# 5_Magnetorquer_Drivers.net
KiCad netlist of a schematic drawn in Altium Designer
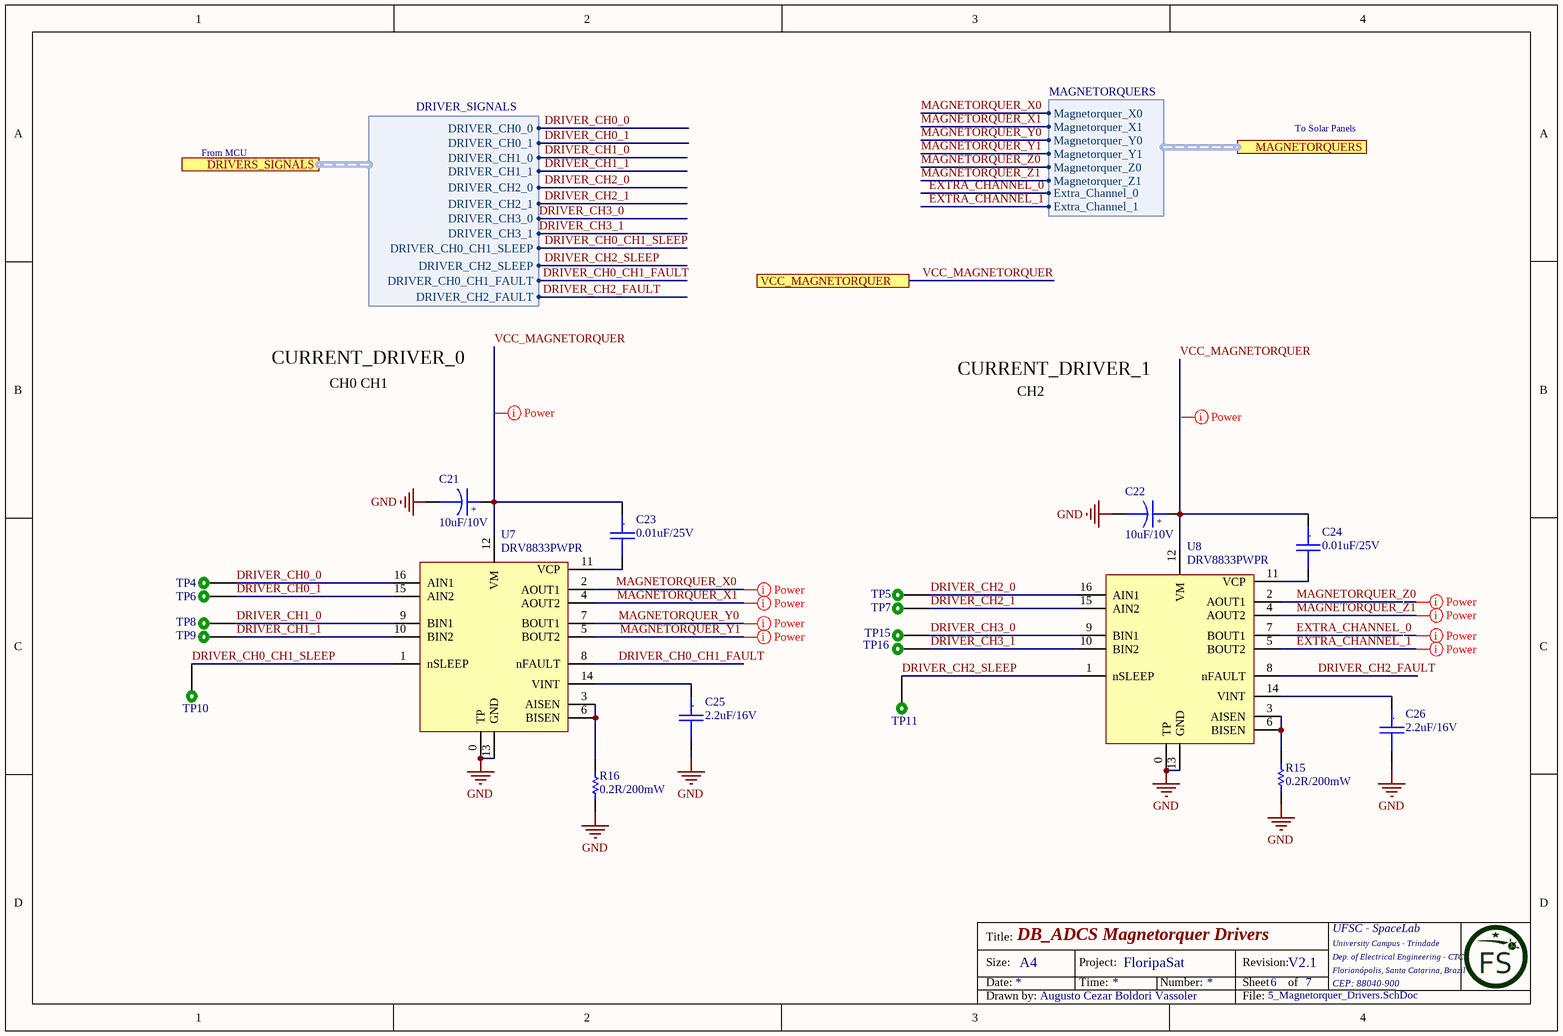
[diagram p0: 5_Magnetorquer_Drivers.SchDoc]

(export (version "E")
  (design (tool "Eeschema 10.0.6"))
  (components
    (comp (ref "C21")
      (value "10uF/10V")
      (footprint "CC0805_Tantalum")
      (description "CAP Tantalum 10uF 6.3V 10% 0805")
      (fields (field (name "PARTNUMBER") "TPSR106K006R1000"))
      (libsource (lib "PCB_Eng_Model_OBDH_2") (part "Cap_Tant_SMD_10uF_6V3_0805"))
    )
    (comp (ref "C22")
      (value "10uF/10V")
      (footprint "CC0805_Tantalum")
      (description "CAP Tantalum 10uF 6.3V 10% 0805")
      (fields (field (name "PARTNUMBER") "TPSR106K006R1000"))
      (libsource (lib "PCB_Eng_Model_OBDH_2") (part "Cap_Tant_SMD_10uF_6V3_0805"))
    )
    (comp (ref "C23")
      (value "0.01uF/25V")
      (footprint "CC0805")
      (description "CAP CER 0.01uF 25V 10% X7R 0805")
      (fields (field (name "PARTNUMBER") "CL21B103KAANNNC"))
      (libsource (lib "PCB_Eng_Model_OBDH_2") (part "Cap_Cer_X7R_0.01uF_50V_0805"))
    )
    (comp (ref "C24")
      (value "0.01uF/25V")
      (footprint "CC0805")
      (description "CAP CER 0.01uF 25V 10% X7R 0805")
      (fields (field (name "PARTNUMBER") "CL21B103KAANNNC"))
      (libsource (lib "PCB_Eng_Model_OBDH_2") (part "Cap_Cer_X7R_0.01uF_50V_0805"))
    )
    (comp (ref "C25")
      (value "2.2uF/16V")
      (footprint "CC0805")
      (description "CAP CER 2.2uF 16V 0805")
      (fields (field (name "PARTNUMBER") "C2012X7R1C225K125AB"))
      (libsource (lib "PCB_Eng_Model_OBDH_2") (part "Cap_Cer_X7R_2.2uF_16V_0805"))
    )
    (comp (ref "C26")
      (value "2.2uF/16V")
      (footprint "CC0805")
      (description "CAP CER 2.2uF 16V 0805")
      (fields (field (name "PARTNUMBER") "C2012X7R1C225K125AB"))
      (libsource (lib "PCB_Eng_Model_OBDH_2") (part "Cap_Cer_X7R_2.2uF_16V_0805"))
    )
    (comp (ref "R15")
      (value "0.2R/200mW")
      (footprint "0805-LED")
      (description "RES 0.2 OHM - 0.2W 1% 0805")
      (fields (field (name "PARTNUMBER") "RL1220S-R20-F"))
      (libsource (lib "PCB_Eng_Model_OBDH_2") (part "R0.015R_1%_0.5W_0805"))
    )
    (comp (ref "R16")
      (value "0.2R/200mW")
      (footprint "0805-LED")
      (description "RES 0.2 OHM - 0.2W 1% 0805")
      (fields (field (name "PARTNUMBER") "RL1220S-R20-F"))
      (libsource (lib "PCB_Eng_Model_OBDH_2") (part "R0.015R_1%_0.5W_0805"))
    )
    (comp (ref "TP4")
      (value "TEST_POINT_2")
      (footprint "TEST_POINT_2")
      (description "Test point")
      (libsource (lib "PCB_Eng_Model_OBDH_2") (part "TEST_POINT_2"))
    )
    (comp (ref "TP5")
      (value "TEST_POINT_2")
      (footprint "TEST_POINT_2")
      (description "Test point")
      (libsource (lib "PCB_Eng_Model_OBDH_2") (part "TEST_POINT_2"))
    )
    (comp (ref "TP6")
      (value "TEST_POINT_2")
      (footprint "TEST_POINT_2")
      (description "Test point")
      (libsource (lib "PCB_Eng_Model_OBDH_2") (part "TEST_POINT_2"))
    )
    (comp (ref "TP7")
      (value "TEST_POINT_2")
      (footprint "TEST_POINT_2")
      (description "Test point")
      (libsource (lib "PCB_Eng_Model_OBDH_2") (part "TEST_POINT_2"))
    )
    (comp (ref "TP8")
      (value "TEST_POINT_2")
      (footprint "TEST_POINT_2")
      (description "Test point")
      (libsource (lib "PCB_Eng_Model_OBDH_2") (part "TEST_POINT_2"))
    )
    (comp (ref "TP9")
      (value "TEST_POINT_2")
      (footprint "TEST_POINT_2")
      (description "Test point")
      (libsource (lib "PCB_Eng_Model_OBDH_2") (part "TEST_POINT_2"))
    )
    (comp (ref "TP10")
      (value "TEST_POINT_2")
      (footprint "TEST_POINT_2")
      (description "Test point")
      (libsource (lib "PCB_Eng_Model_OBDH_2") (part "TEST_POINT_2"))
    )
    (comp (ref "TP11")
      (value "TEST_POINT_2")
      (footprint "TEST_POINT_2")
      (description "Test point")
      (libsource (lib "PCB_Eng_Model_OBDH_2") (part "TEST_POINT_2"))
    )
    (comp (ref "TP15")
      (value "TEST_POINT_2")
      (footprint "TEST_POINT_2")
      (description "Test point")
      (libsource (lib "PCB_DB_ADCS") (part "TEST_POINT_2"))
    )
    (comp (ref "TP16")
      (value "TEST_POINT_2")
      (footprint "TEST_POINT_2")
      (description "Test point")
      (libsource (lib "PCB_DB_ADCS") (part "TEST_POINT_2"))
    )
    (comp (ref "U7")
      (value "DRV8833PWPR")
      (footprint "16TTSSOP")
      (libsource (lib "FloripaSatSchlib") (part "DRV8833PWPR"))
    )
    (comp (ref "U8")
      (value "DRV8833PWPR")
      (footprint "16TTSSOP")
      (libsource (lib "FloripaSatSchlib") (part "DRV8833PWPR"))
    )
  )
  (nets
    (net (code "3") (name "/DRIVER_CH0_0") (class "Default")
      (node (ref "TP4") (pin "1") (pinfunction "1_1") (pintype "passive"))
      (node (ref "U7") (pin "16") (pinfunction "AIN1_16") (pintype "passive"))
    )
    (net (code "4") (name "/DRIVER_CH0_1") (class "Default")
      (node (ref "TP6") (pin "1") (pinfunction "1_1") (pintype "passive"))
      (node (ref "U7") (pin "15") (pinfunction "AIN2_15") (pintype "passive"))
    )
    (net (code "5") (name "/DRIVER_CH0_CH1_FAULT") (class "Default")
      (node (ref "U7") (pin "8") (pinfunction "nFAULT_8") (pintype "passive"))
    )
    (net (code "6") (name "/DRIVER_CH0_CH1_SLEEP") (class "Default")
      (node (ref "TP10") (pin "1") (pinfunction "1_1") (pintype "passive"))
      (node (ref "U7") (pin "1") (pinfunction "nSLEEP_1") (pintype "passive"))
    )
    (net (code "7") (name "/DRIVER_CH1_0") (class "Default")
      (node (ref "TP8") (pin "1") (pinfunction "1_1") (pintype "passive"))
      (node (ref "U7") (pin "9") (pinfunction "BIN1_9") (pintype "passive"))
    )
    (net (code "8") (name "/DRIVER_CH1_1") (class "Default")
      (node (ref "TP9") (pin "1") (pinfunction "1_1") (pintype "passive"))
      (node (ref "U7") (pin "10") (pinfunction "BIN2_10") (pintype "passive"))
    )
    (net (code "9") (name "/DRIVER_CH2_0") (class "Default")
      (node (ref "TP5") (pin "1") (pinfunction "1_1") (pintype "passive"))
      (node (ref "U8") (pin "16") (pinfunction "AIN1_16") (pintype "passive"))
    )
    (net (code "10") (name "/DRIVER_CH2_1") (class "Default")
      (node (ref "TP7") (pin "1") (pinfunction "1_1") (pintype "passive"))
      (node (ref "U8") (pin "15") (pinfunction "AIN2_15") (pintype "passive"))
    )
    (net (code "11") (name "/DRIVER_CH2_FAULT") (class "Default")
      (node (ref "U8") (pin "8") (pinfunction "nFAULT_8") (pintype "passive"))
    )
    (net (code "12") (name "/DRIVER_CH2_SLEEP") (class "Default")
      (node (ref "TP11") (pin "1") (pinfunction "1_1") (pintype "passive"))
      (node (ref "U8") (pin "1") (pinfunction "nSLEEP_1") (pintype "passive"))
    )
    (net (code "13") (name "/DRIVER_CH3_0") (class "Default")
      (node (ref "TP15") (pin "1") (pinfunction "1_1") (pintype "passive"))
      (node (ref "U8") (pin "9") (pinfunction "BIN1_9") (pintype "passive"))
    )
    (net (code "14") (name "/DRIVER_CH3_1") (class "Default")
      (node (ref "TP16") (pin "1") (pinfunction "1_1") (pintype "passive"))
      (node (ref "U8") (pin "10") (pinfunction "BIN2_10") (pintype "passive"))
    )
    (net (code "15") (name "/EXTRA_CHANNEL_0") (class "Default")
      (node (ref "U8") (pin "7") (pinfunction "BOUT1_7") (pintype "passive"))
    )
    (net (code "16") (name "/EXTRA_CHANNEL_1") (class "Default")
      (node (ref "U8") (pin "5") (pinfunction "BOUT2_5") (pintype "passive"))
    )
    (net (code "17") (name "/MAGNETORQUER_X0") (class "Default")
      (node (ref "U7") (pin "2") (pinfunction "AOUT1_2") (pintype "passive"))
    )
    (net (code "18") (name "/MAGNETORQUER_X1") (class "Default")
      (node (ref "U7") (pin "4") (pinfunction "AOUT2_4") (pintype "passive"))
    )
    (net (code "19") (name "/MAGNETORQUER_Y0") (class "Default")
      (node (ref "U7") (pin "7") (pinfunction "BOUT1_7") (pintype "passive"))
    )
    (net (code "20") (name "/MAGNETORQUER_Y1") (class "Default")
      (node (ref "U7") (pin "5") (pinfunction "BOUT2_5") (pintype "passive"))
    )
    (net (code "21") (name "/MAGNETORQUER_Z0") (class "Default")
      (node (ref "U8") (pin "2") (pinfunction "AOUT1_2") (pintype "passive"))
    )
    (net (code "22") (name "/MAGNETORQUER_Z1") (class "Default")
      (node (ref "U8") (pin "4") (pinfunction "AOUT2_4") (pintype "passive"))
    )
    (net (code "23") (name "/VCC_MAGNETORQUER") (class "Default")
      (node (ref "C21") (pin "1") (pinfunction "1_1") (pintype "passive"))
      (node (ref "C22") (pin "1") (pinfunction "1_1") (pintype "passive"))
      (node (ref "C23") (pin "1") (pinfunction "1_1") (pintype "passive"))
      (node (ref "C24") (pin "1") (pinfunction "1_1") (pintype "passive"))
      (node (ref "U7") (pin "12") (pinfunction "VM_12") (pintype "passive"))
      (node (ref "U8") (pin "12") (pinfunction "VM_12") (pintype "passive"))
    )
    (net (code "26") (name "GND") (class "Default")
      (node (ref "C21") (pin "2") (pinfunction "2_2") (pintype "passive"))
      (node (ref "C22") (pin "2") (pinfunction "2_2") (pintype "passive"))
      (node (ref "C25") (pin "2") (pinfunction "2_2") (pintype "passive"))
      (node (ref "C26") (pin "2") (pinfunction "2_2") (pintype "passive"))
      (node (ref "R15") (pin "1") (pinfunction "1_1") (pintype "passive"))
      (node (ref "R16") (pin "1") (pinfunction "1_1") (pintype "passive"))
      (node (ref "U7") (pin "0") (pinfunction "TP_0") (pintype "passive"))
      (node (ref "U7") (pin "13") (pinfunction "GND_13") (pintype "passive"))
      (node (ref "U8") (pin "0") (pinfunction "TP_0") (pintype "passive"))
      (node (ref "U8") (pin "13") (pinfunction "GND_13") (pintype "passive"))
    )
    (net (code "27") (name "Net-(U7-AISEN)") (class "Default")
      (node (ref "R16") (pin "2") (pinfunction "2_2") (pintype "passive"))
      (node (ref "U7") (pin "3") (pinfunction "AISEN_3") (pintype "passive"))
      (node (ref "U7") (pin "6") (pinfunction "BISEN_6") (pintype "passive"))
    )
    (net (code "28") (name "Net-(U7-VCP)") (class "Default")
      (node (ref "C23") (pin "2") (pinfunction "2_2") (pintype "passive"))
      (node (ref "U7") (pin "11") (pinfunction "VCP_11") (pintype "passive"))
    )
    (net (code "29") (name "Net-(U7-VINT)") (class "Default")
      (node (ref "C25") (pin "1") (pinfunction "1_1") (pintype "passive"))
      (node (ref "U7") (pin "14") (pinfunction "VINT_14") (pintype "passive"))
    )
    (net (code "30") (name "Net-(U8-AISEN)") (class "Default")
      (node (ref "R15") (pin "2") (pinfunction "2_2") (pintype "passive"))
      (node (ref "U8") (pin "3") (pinfunction "AISEN_3") (pintype "passive"))
      (node (ref "U8") (pin "6") (pinfunction "BISEN_6") (pintype "passive"))
    )
    (net (code "31") (name "Net-(U8-VCP)") (class "Default")
      (node (ref "C24") (pin "2") (pinfunction "2_2") (pintype "passive"))
      (node (ref "U8") (pin "11") (pinfunction "VCP_11") (pintype "passive"))
    )
    (net (code "32") (name "Net-(U8-VINT)") (class "Default")
      (node (ref "C26") (pin "1") (pinfunction "1_1") (pintype "passive"))
      (node (ref "U8") (pin "14") (pinfunction "VINT_14") (pintype "passive"))
    )
  )
)
